# EAT0002.net
KiCad netlist of a schematic drawn in EAGLE
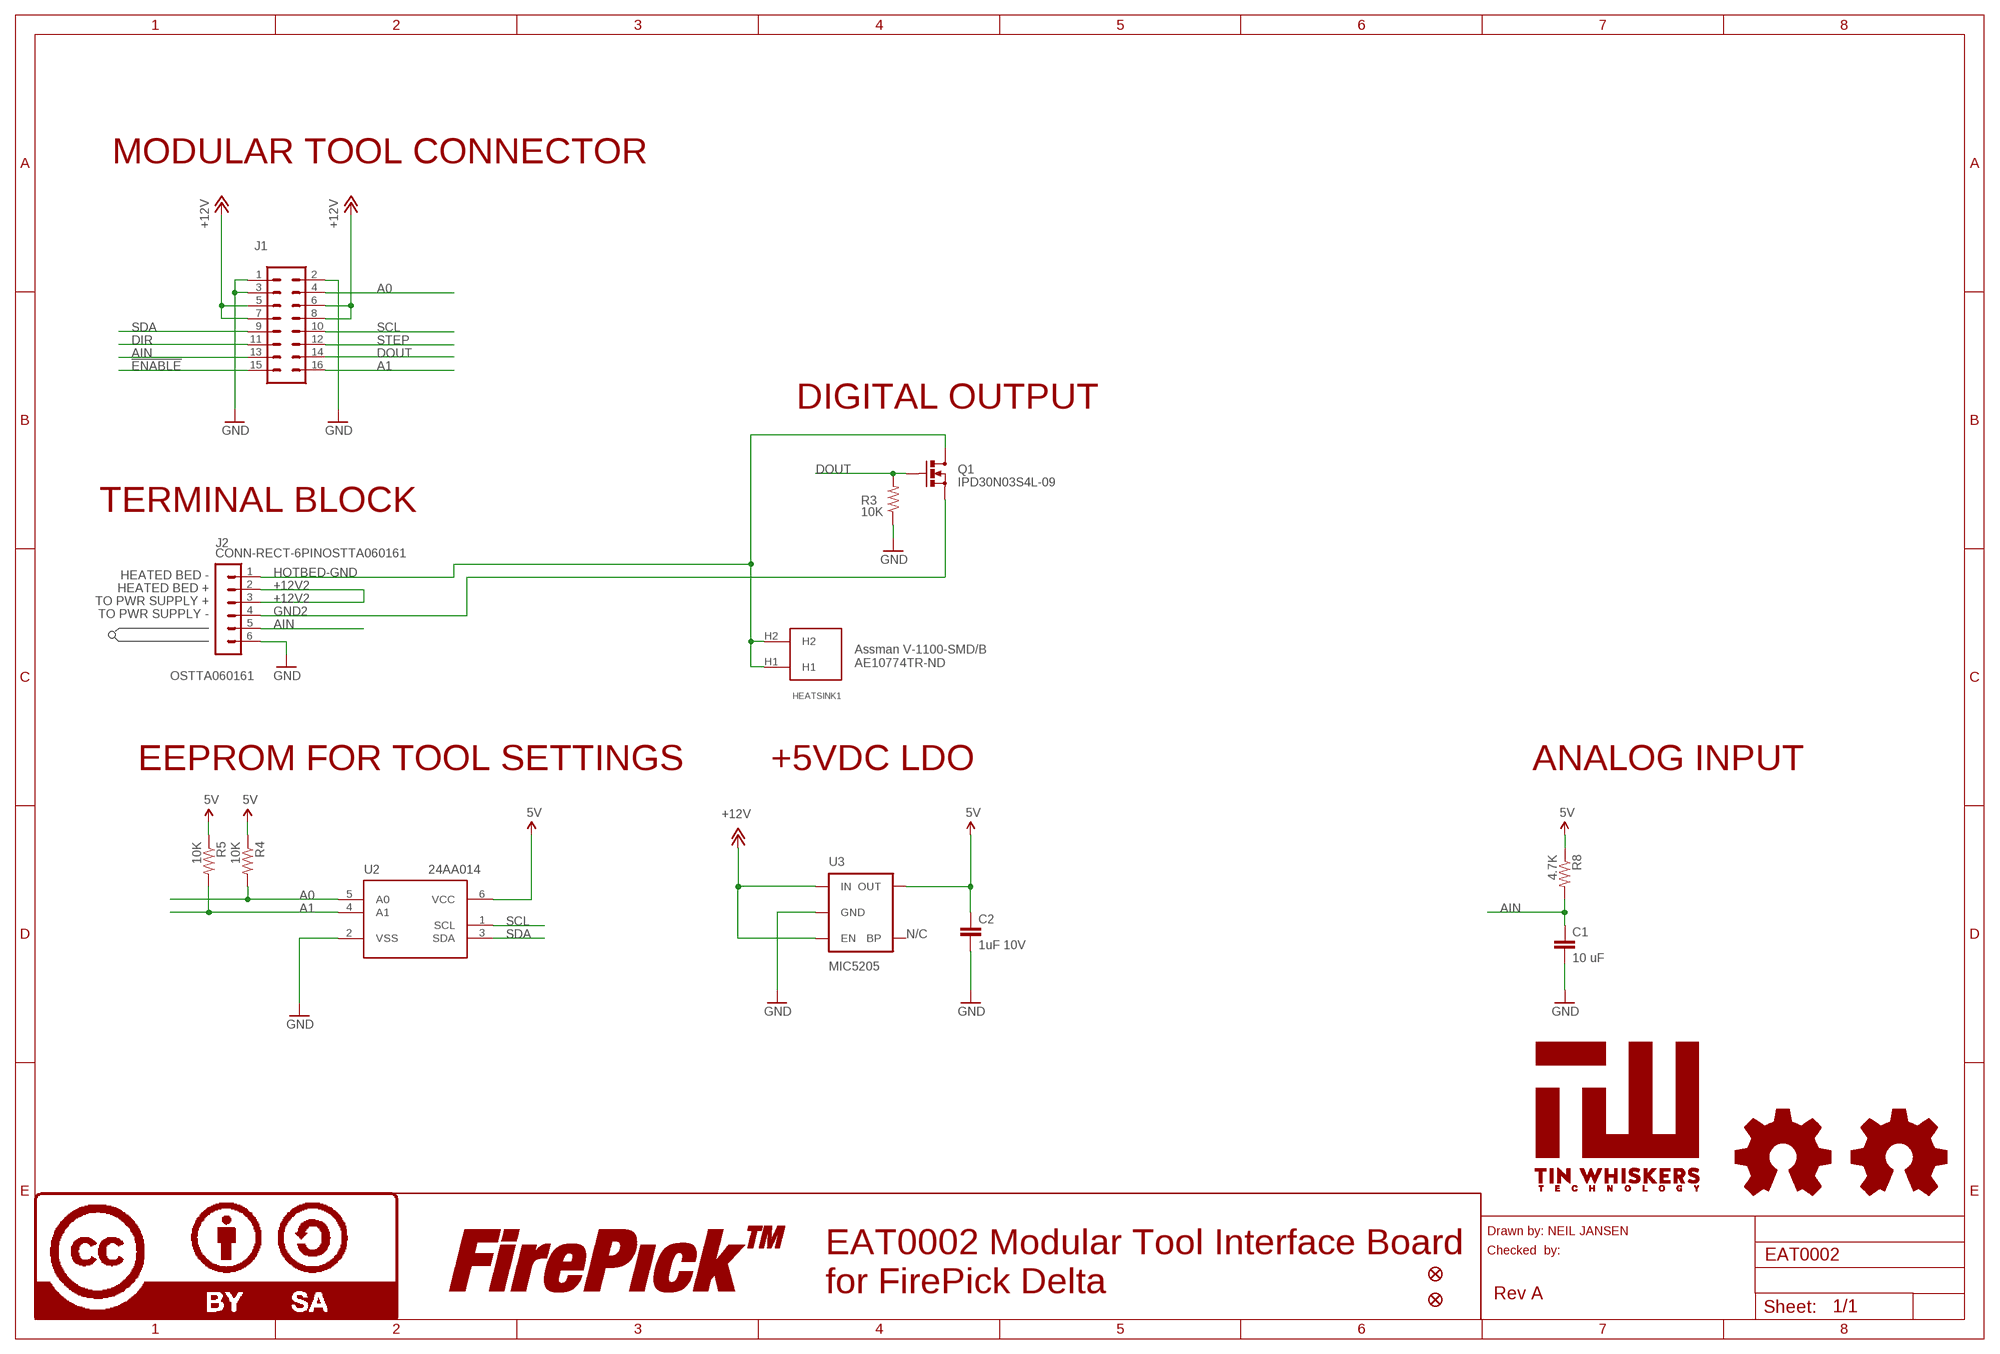
[diagram p0: schematic, sheet 1]

(export (version "E")
  (design (tool "Eeschema 10.0.6"))
  (components
    (comp (ref "C1")
      (value "10 uF")
      (footprint "eagle-import:0805")
      (fields (field (name "PARTNO") "CC0805ZKY5V6BB106"))
      (libsource (lib "eagle-import") (part "CAP0805"))
    )
    (comp (ref "C2")
      (value "1uF 10V")
      (footprint "eagle-import:0805")
      (fields (field (name "PARTNO") "CC0805KKX7R7BB105"))
      (libsource (lib "eagle-import") (part "CAP0805"))
    )
    (comp (ref "FID1")
      (value "FIDUCIAL")
      (footprint "eagle-import:FIDUCIAL")
      (libsource (lib "eagle-import") (part "FIDUCIAL"))
    )
    (comp (ref "FID2")
      (value "FIDUCIAL")
      (footprint "eagle-import:FIDUCIAL")
      (libsource (lib "eagle-import") (part "FIDUCIAL"))
    )
    (comp (ref "HEATSINK1")
      (value "HEATSINK-DPAK")
      (footprint "eagle-import:HEATSINK-DPAK")
      (fields (field (name "PARTNO") "V-1100-SMD/B"))
      (libsource (lib "eagle-import") (part "HEATSINK-DPAK"))
    )
    (comp (ref "J1")
      (value "CONN-RECT-16PIN-2ROWSIDE")
      (footprint "eagle-import:CONN-RECT-2.54MM-16PIN-2ROW-SIDE")
      (fields (field (name "PARTNO") "CONN-0.1-S-2x8"))
      (libsource (lib "eagle-import") (part "CONN-RECT-16PIN-2ROWSIDE"))
    )
    (comp (ref "J2")
      (value "CONN-RECT-6PINOSTTA060161")
      (footprint "eagle-import:CONN-OSTTA060161")
      (fields (field (name "PARTNO") "OSTTA060161"))
      (libsource (lib "eagle-import") (part "CONN-RECT-6PINOSTTA060161"))
    )
    (comp (ref "LOGO1")
      (value "LOGO-OSHWSMALL")
      (footprint "eagle-import:LOGO-OSHW-SMALL")
      (libsource (lib "eagle-import") (part "LOGO-OSHWSMALL"))
    )
    (comp (ref "LOGO4")
      (value "LOGO-FIREPICKMEDIUM")
      (footprint "eagle-import:LOGO-FIREPICK-MEDIUM")
      (libsource (lib "eagle-import") (part "LOGO-FIREPICKMEDIUM"))
    )
    (comp (ref "LOGO5")
      (value "LOGO-OSHWSMALL")
      (footprint "eagle-import:LOGO-OSHW-SMALL")
      (libsource (lib "eagle-import") (part "LOGO-OSHWSMALL"))
    )
    (comp (ref "LOGO6")
      (value "LOGO-CC-BY-SAMEDIUM")
      (footprint "eagle-import:LOGO-CC-BY-SA-MEDIUM")
      (libsource (lib "eagle-import") (part "LOGO-CC-BY-SAMEDIUM"))
    )
    (comp (ref "Q1")
      (value "IPD30N03S4L-09")
      (footprint "eagle-import:DPAK")
      (libsource (lib "eagle-import") (part "MOSFET-NCHANNELFDD8580"))
    )
    (comp (ref "R3")
      (value "10K")
      (footprint "eagle-import:0805")
      (fields (field (name "PARTNO") "RC0805FR-0710KL"))
      (libsource (lib "eagle-import") (part "RESISTOR0805-RES"))
    )
    (comp (ref "R4")
      (value "10K")
      (footprint "eagle-import:0805")
      (fields (field (name "PARTNO") "RC0805FR-0710KL"))
      (libsource (lib "eagle-import") (part "RESISTOR0805-RES"))
    )
    (comp (ref "R5")
      (value "10K")
      (footprint "eagle-import:0805")
      (fields (field (name "PARTNO") "RC0805FR-0710KL"))
      (libsource (lib "eagle-import") (part "RESISTOR0805-RES"))
    )
    (comp (ref "R8")
      (value "4.7K")
      (footprint "eagle-import:0805")
      (fields (field (name "PARTNO") "RC0805FR-074K7L"))
      (libsource (lib "eagle-import") (part "RESISTOR0805-RES"))
    )
    (comp (ref "U$1")
      (value "TIN-WHISKERSSMALL")
      (footprint "eagle-import:TIN-WHISKERS-SMALL")
      (libsource (lib "eagle-import") (part "TIN-WHISKERSSMALL"))
    )
    (comp (ref "U2")
      (value "24AA014")
      (footprint "eagle-import:SOT23-6")
      (fields (field (name "PARTNO") "24AA014T-I/OT"))
      (libsource (lib "eagle-import") (part "IC-24AA014"))
    )
    (comp (ref "U3")
      (value "MIC5205")
      (footprint "eagle-import:SOT23-5")
      (fields (field (name "PARTNO") "MIC5205-5.0YM5 TR"))
      (libsource (lib "eagle-import") (part "MIC52055V"))
    )
  )
  (nets
    (net (code "1") (name "+12V") (class "Default")
      (node (ref "J1") (pin "5") (pinfunction "5_5") (pintype "passive"))
      (node (ref "J1") (pin "6") (pinfunction "6_6") (pintype "passive"))
      (node (ref "J1") (pin "7") (pinfunction "7_7") (pintype "passive"))
      (node (ref "J1") (pin "8") (pinfunction "8_8") (pintype "passive"))
      (node (ref "U3") (pin "1") (pinfunction "IN_1") (pintype "input"))
      (node (ref "U3") (pin "3") (pinfunction "EN_3") (pintype "input"))
    )
    (net (code "2") (name "/+12V2") (class "Default")
      (node (ref "J2") (pin "2") (pinfunction "2_2") (pintype "passive"))
      (node (ref "J2") (pin "3") (pinfunction "3_3") (pintype "passive"))
    )
    (net (code "3") (name "/A0") (class "Default")
      (node (ref "J1") (pin "4") (pinfunction "4_4") (pintype "passive"))
      (node (ref "R4") (pin "2") (pinfunction "2_2") (pintype "passive"))
      (node (ref "U2") (pin "5") (pinfunction "A0_5") (pintype "bidirectional"))
    )
    (net (code "4") (name "/A1") (class "Default")
      (node (ref "J1") (pin "16") (pinfunction "16_16") (pintype "passive"))
      (node (ref "R5") (pin "2") (pinfunction "2_2") (pintype "passive"))
      (node (ref "U2") (pin "4") (pinfunction "A1_4") (pintype "bidirectional"))
    )
    (net (code "5") (name "/AIN") (class "Default")
      (node (ref "C1") (pin "1") (pinfunction "1_1") (pintype "passive"))
      (node (ref "J1") (pin "13") (pinfunction "13_13") (pintype "passive"))
      (node (ref "J2") (pin "5") (pinfunction "5_5") (pintype "passive"))
      (node (ref "R8") (pin "2") (pinfunction "2_2") (pintype "passive"))
    )
    (net (code "6") (name "/DIR") (class "Default")
      (node (ref "J1") (pin "11") (pinfunction "11_11") (pintype "passive"))
    )
    (net (code "7") (name "/DOUT") (class "Default")
      (node (ref "J1") (pin "14") (pinfunction "14_14") (pintype "passive"))
      (node (ref "Q1") (pin "1") (pinfunction "G_1") (pintype "passive"))
      (node (ref "R3") (pin "2") (pinfunction "2_2") (pintype "passive"))
    )
    (net (code "8") (name "/GND2") (class "Default")
      (node (ref "J2") (pin "4") (pinfunction "4_4") (pintype "passive"))
      (node (ref "Q1") (pin "3") (pinfunction "S_3") (pintype "passive"))
    )
    (net (code "9") (name "/HOTBED-GND") (class "Default")
      (node (ref "HEATSINK1") (pin "H1") (pinfunction "H1_H1") (pintype "bidirectional"))
      (node (ref "HEATSINK1") (pin "H2") (pinfunction "H2_H2") (pintype "bidirectional"))
      (node (ref "J2") (pin "1") (pinfunction "1_1") (pintype "passive"))
      (node (ref "Q1") (pin "4") (pinfunction "D_4") (pintype "passive"))
    )
    (net (code "10") (name "/SCL") (class "Default")
      (node (ref "J1") (pin "10") (pinfunction "10_10") (pintype "passive"))
      (node (ref "U2") (pin "1") (pinfunction "SCL_1") (pintype "bidirectional"))
    )
    (net (code "11") (name "/SDA") (class "Default")
      (node (ref "J1") (pin "9") (pinfunction "9_9") (pintype "passive"))
      (node (ref "U2") (pin "3") (pinfunction "SDA_3") (pintype "bidirectional"))
    )
    (net (code "12") (name "/STEP") (class "Default")
      (node (ref "J1") (pin "12") (pinfunction "12_12") (pintype "passive"))
    )
    (net (code "13") (name "/~{ENABLE}") (class "Default")
      (node (ref "J1") (pin "15") (pinfunction "15_15") (pintype "passive"))
    )
    (net (code "14") (name "5V") (class "Default")
      (node (ref "C2") (pin "1") (pinfunction "1_1") (pintype "passive"))
      (node (ref "R4") (pin "1") (pinfunction "1_1") (pintype "passive"))
      (node (ref "R5") (pin "1") (pinfunction "1_1") (pintype "passive"))
      (node (ref "R8") (pin "1") (pinfunction "1_1") (pintype "passive"))
      (node (ref "U2") (pin "6") (pinfunction "VCC_6") (pintype "bidirectional"))
      (node (ref "U3") (pin "5") (pinfunction "OUT_5") (pintype "passive"))
    )
    (net (code "15") (name "GND") (class "Default")
      (node (ref "C1") (pin "2") (pinfunction "2_2") (pintype "passive"))
      (node (ref "C2") (pin "2") (pinfunction "2_2") (pintype "passive"))
      (node (ref "J1") (pin "1") (pinfunction "1_1") (pintype "passive"))
      (node (ref "J1") (pin "2") (pinfunction "2_2") (pintype "passive"))
      (node (ref "J1") (pin "3") (pinfunction "3_3") (pintype "passive"))
      (node (ref "J2") (pin "6") (pinfunction "6_6") (pintype "passive"))
      (node (ref "R3") (pin "1") (pinfunction "1_1") (pintype "passive"))
      (node (ref "U2") (pin "2") (pinfunction "VSS_2") (pintype "bidirectional"))
      (node (ref "U3") (pin "2") (pinfunction "GND_2") (pintype "input"))
    )
    (net (code "16") (name "unconnected-(U3-BP-Pad4)") (class "Default")
      (node (ref "U3") (pin "4") (pinfunction "BP_4") (pintype "input"))
    )
  )
)
